# powermeter.net
KiCad netlist of a schematic drawn in EAGLE
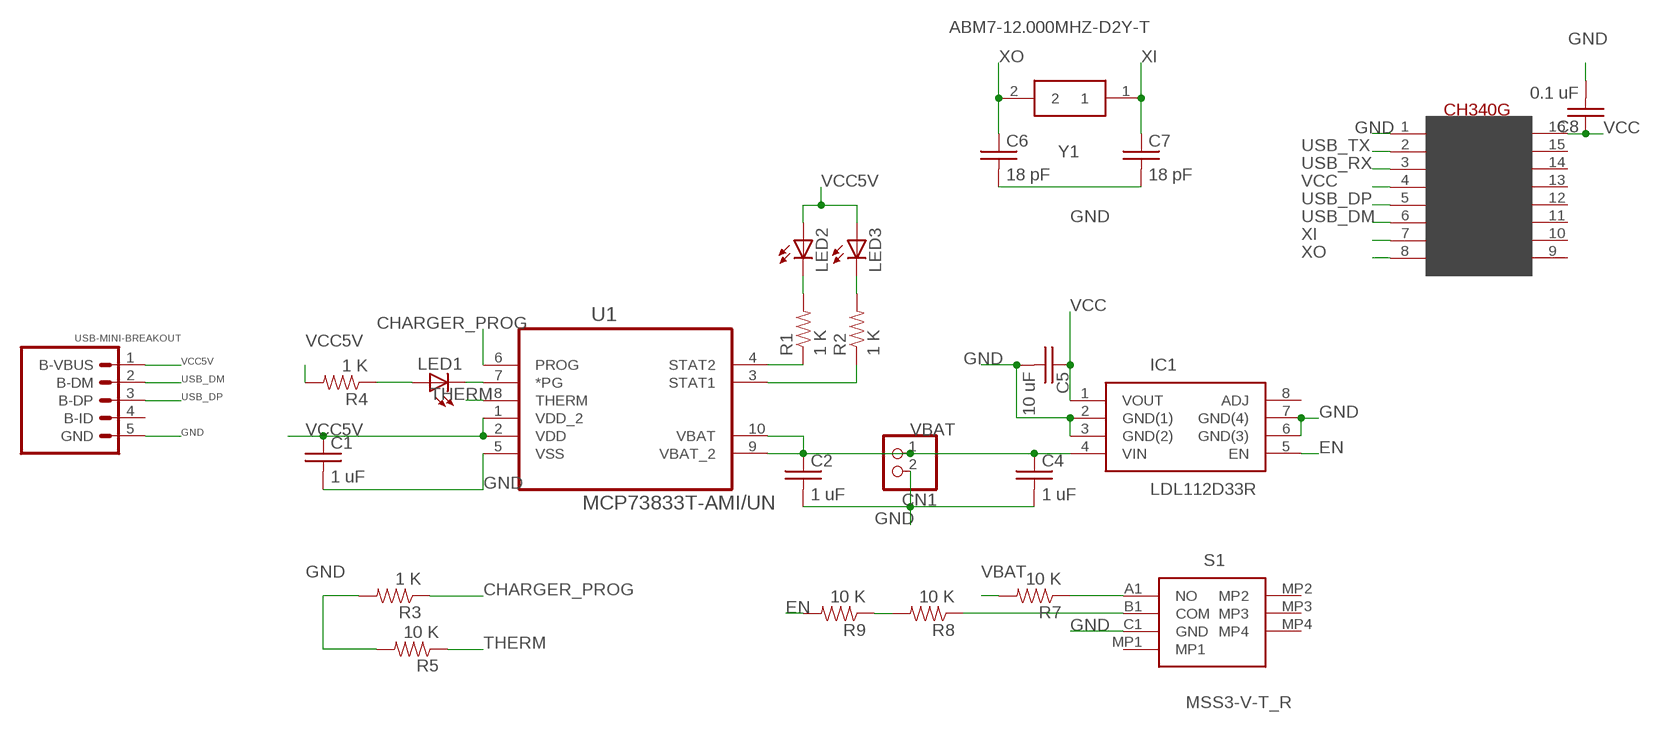
[diagram p0: schematic, sheet 1]
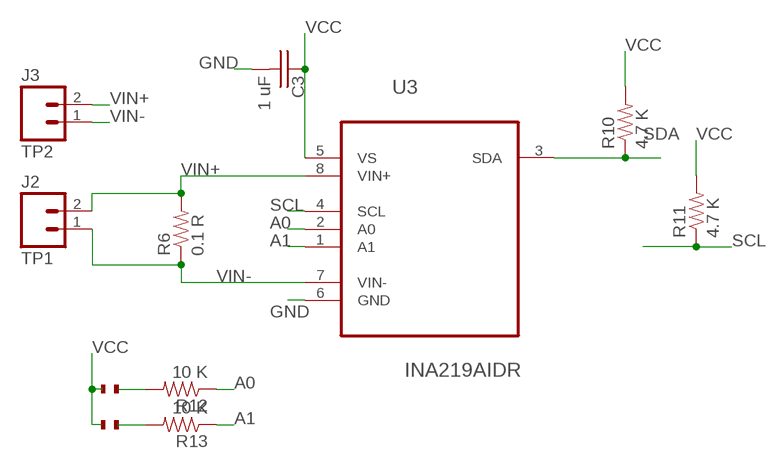
[diagram p1: schematic, sheet 2]
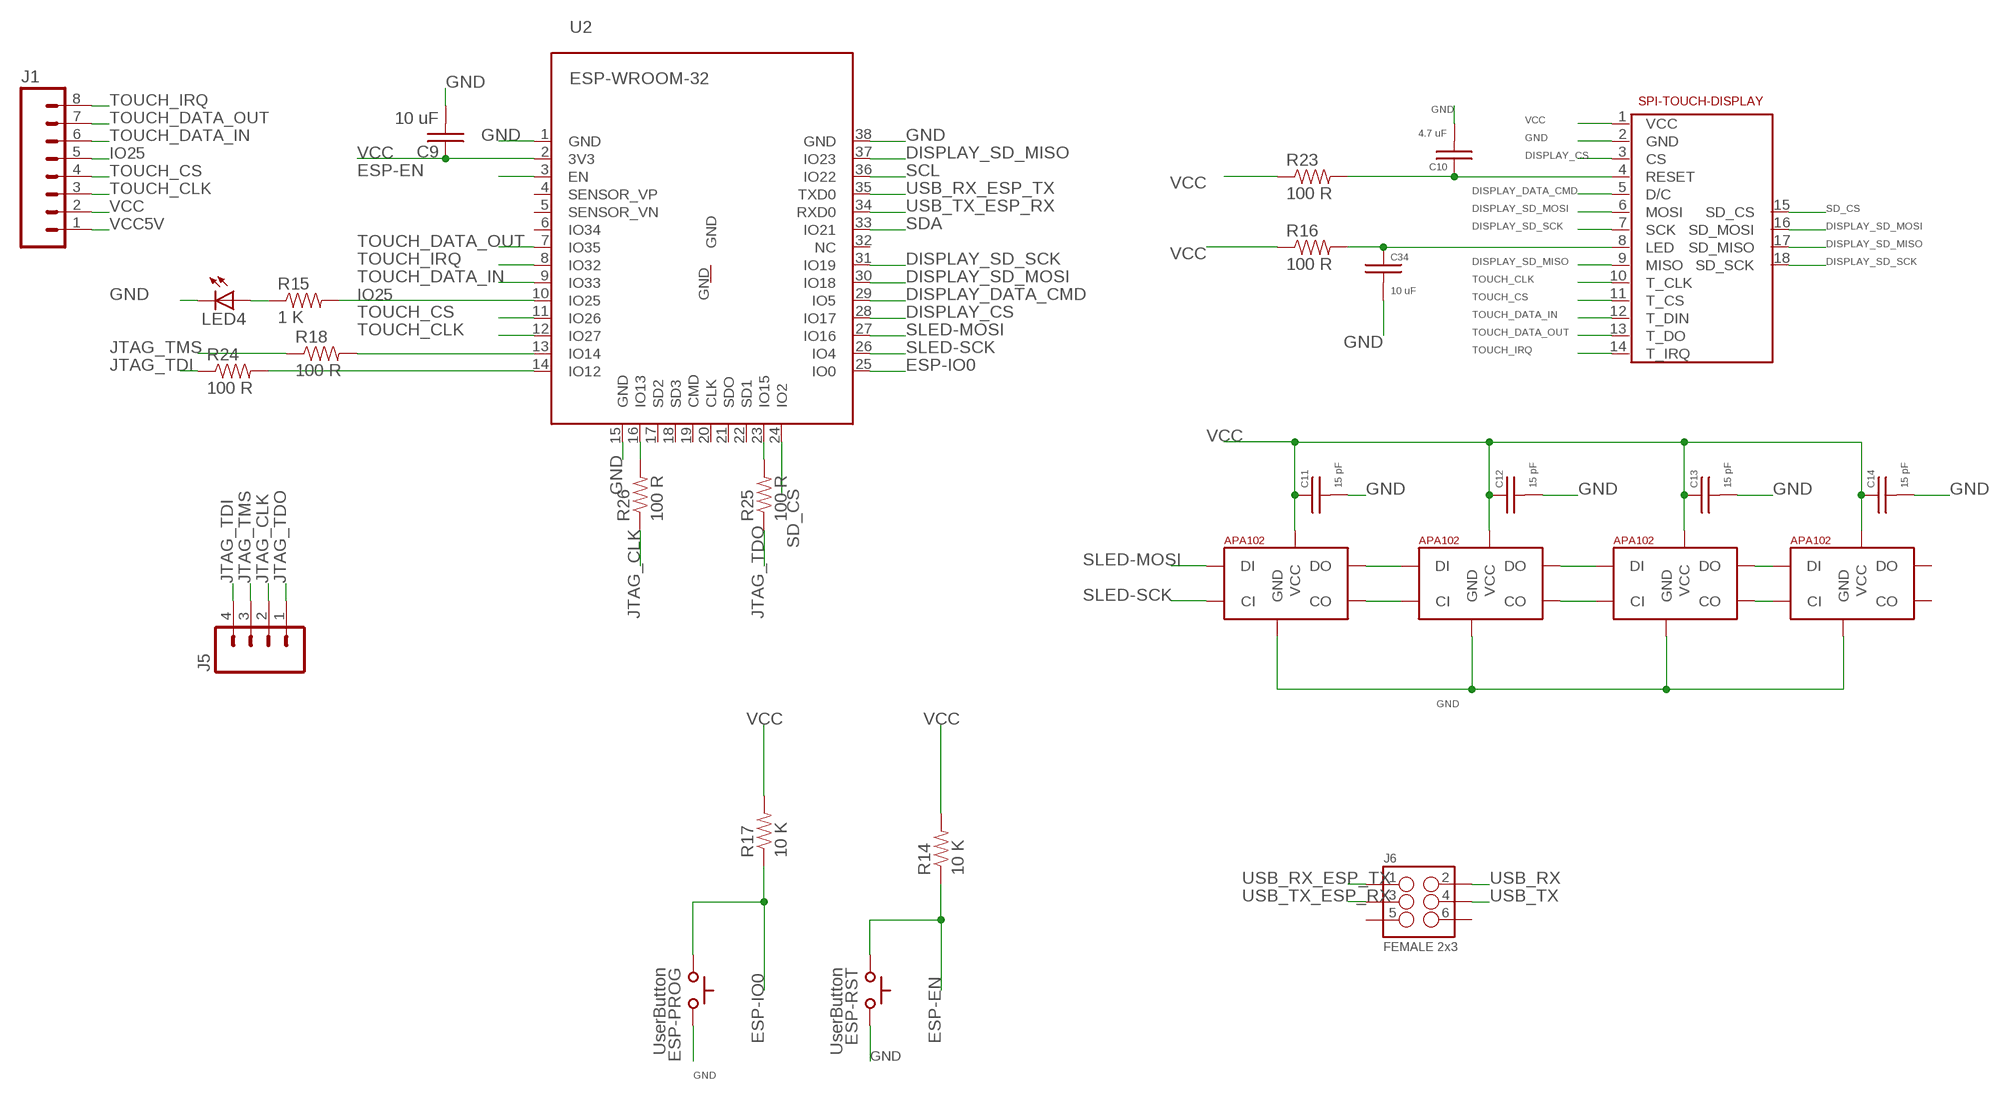
[diagram p2: schematic, sheet 3]

(export (version "E")
  (design (tool "Eeschema 10.0.6"))
  (components
    (comp (ref "C9")
      (value "10 uF")
      (footprint "eagle-import:C0805K")
      (libsource (lib "eagle-import") (part "C-USC0805K"))
    )
    (comp (ref "C10")
      (value "4.7 uF")
      (footprint "eagle-import:C0805")
      (libsource (lib "eagle-import") (part "C-USC0805"))
    )
    (comp (ref "C11")
      (value "15 pF")
      (footprint "eagle-import:C0805")
      (libsource (lib "eagle-import") (part "C-USC0805"))
    )
    (comp (ref "C12")
      (value "15 pF")
      (footprint "eagle-import:C0805")
      (libsource (lib "eagle-import") (part "C-USC0805"))
    )
    (comp (ref "C13")
      (value "15 pF")
      (footprint "eagle-import:C0805")
      (libsource (lib "eagle-import") (part "C-USC0805"))
    )
    (comp (ref "C14")
      (value "15 pF")
      (footprint "eagle-import:C0805")
      (libsource (lib "eagle-import") (part "C-USC0805"))
    )
    (comp (ref "C34")
      (value "10 uF")
      (footprint "eagle-import:C0805")
      (libsource (lib "eagle-import") (part "C-USC0805"))
    )
    (comp (ref "ESP-PROG")
      (value "UserButton")
      (footprint "eagle-import:TACTILE-2PIN-NARROW")
      (libsource (lib "eagle-import") (part "SWITCH_TACTILETACTILE-2PIN-NARROW"))
    )
    (comp (ref "ESP-RST")
      (value "UserButton")
      (footprint "eagle-import:TACTILE-2PIN-NARROW")
      (libsource (lib "eagle-import") (part "SWITCH_TACTILETACTILE-2PIN-NARROW"))
    )
    (comp (ref "J1")
      (value "M08LONGPADS")
      (footprint "eagle-import:1X08_LONGPADS")
      (libsource (lib "eagle-import") (part "M08LONGPADS"))
    )
    (comp (ref "J5")
      (value "M04LONGPADS")
      (footprint "eagle-import:1X04_LONGPADS")
      (libsource (lib "eagle-import") (part "M04LONGPADS"))
    )
    (comp (ref "J6")
      (value "FEMALE 2x3")
      (footprint "eagle-import:2X3")
      (libsource (lib "eagle-import") (part "M03X2FEMALE"))
    )
    (comp (ref "LED4")
      (value "LED1206")
      (footprint "eagle-import:LED-1206")
      (libsource (lib "eagle-import") (part "LED1206"))
    )
    (comp (ref "R14")
      (value "10 K")
      (footprint "eagle-import:R0805")
      (libsource (lib "eagle-import") (part "RESISTORR0805-RES"))
    )
    (comp (ref "R15")
      (value "1 K")
      (footprint "eagle-import:R0805")
      (libsource (lib "eagle-import") (part "RESISTORR0805-RES"))
    )
    (comp (ref "R16")
      (value "100 R")
      (footprint "eagle-import:R0805")
      (libsource (lib "eagle-import") (part "RESISTORR0805-RES"))
    )
    (comp (ref "R17")
      (value "10 K")
      (footprint "eagle-import:R0805")
      (libsource (lib "eagle-import") (part "RESISTORR0805-RES"))
    )
    (comp (ref "R18")
      (value "100 R")
      (footprint "eagle-import:R0805")
      (libsource (lib "eagle-import") (part "RESISTORR0805-RES"))
    )
    (comp (ref "R23")
      (value "100 R")
      (footprint "eagle-import:R0805")
      (libsource (lib "eagle-import") (part "RESISTORR0805-RES"))
    )
    (comp (ref "R24")
      (value "100 R")
      (footprint "eagle-import:R0805")
      (libsource (lib "eagle-import") (part "RESISTORR0805-RES"))
    )
    (comp (ref "R25")
      (value "100 R")
      (footprint "eagle-import:R0805")
      (libsource (lib "eagle-import") (part "RESISTORR0805-RES"))
    )
    (comp (ref "R26")
      (value "100 R")
      (footprint "eagle-import:R0805")
      (libsource (lib "eagle-import") (part "RESISTORR0805-RES"))
    )
    (comp (ref "U$3")
      (value "2.4-SPI-TFT-TOUCH-SSD-MODULE")
      (footprint "eagle-import:2.4-SPI-TFT-TOUCH-SSD-MODULE")
      (libsource (lib "eagle-import") (part "2.4-SPI-TFT-TOUCH-SSD-MODULE"))
    )
    (comp (ref "U$5")
      (value "APA1025050")
      (footprint "eagle-import:APA102_5050")
      (libsource (lib "eagle-import") (part "APA1025050"))
    )
    (comp (ref "U$6")
      (value "APA1025050")
      (footprint "eagle-import:APA102_5050")
      (libsource (lib "eagle-import") (part "APA1025050"))
    )
    (comp (ref "U$7")
      (value "APA1025050")
      (footprint "eagle-import:APA102_5050")
      (libsource (lib "eagle-import") (part "APA1025050"))
    )
    (comp (ref "U$8")
      (value "APA1025050")
      (footprint "eagle-import:APA102_5050")
      (libsource (lib "eagle-import") (part "APA1025050"))
    )
    (comp (ref "U2")
      (value "ESP-WROOM-32")
      (footprint "eagle-import:ESP-WROOM-32")
      (libsource (lib "eagle-import") (part "ESP-WROOM-32"))
    )
    (comp (ref "C1")
      (value "1 uF")
      (footprint "eagle-import:C0805K")
      (libsource (lib "eagle-import") (part "C-USC0805K"))
    )
    (comp (ref "C2")
      (value "1 uF")
      (footprint "eagle-import:C0805K")
      (libsource (lib "eagle-import") (part "C-USC0805K"))
    )
    (comp (ref "C4")
      (value "1 uF")
      (footprint "eagle-import:C0805K")
      (libsource (lib "eagle-import") (part "C-USC0805K"))
    )
    (comp (ref "C5")
      (value "10 uF")
      (footprint "eagle-import:C0805K")
      (libsource (lib "eagle-import") (part "C-USC0805K"))
    )
    (comp (ref "C6")
      (value "18 pF")
      (footprint "eagle-import:C0805K")
      (libsource (lib "eagle-import") (part "C-USC0805K"))
    )
    (comp (ref "C7")
      (value "18 pF")
      (footprint "eagle-import:C0805K")
      (libsource (lib "eagle-import") (part "C-USC0805K"))
    )
    (comp (ref "C8")
      (value "0.1 uF")
      (footprint "eagle-import:C0805K")
      (libsource (lib "eagle-import") (part "C-USC0805K"))
    )
    (comp (ref "CN1")
      (value "JST_2PIN-THM-RA")
      (footprint "eagle-import:JST-PH-2-THM-RA")
      (libsource (lib "eagle-import") (part "JST_2PIN-THM-RA"))
    )
    (comp (ref "IC1")
      (value "LDL112D33R")
      (footprint "eagle-import:SOIC127P600X175-8N")
      (libsource (lib "eagle-import") (part "LDL112D33R"))
    )
    (comp (ref "LED1")
      (value "LEDXZCFBB53W-8VF-2MA-LED")
      (footprint "eagle-import:LEDC1606X95N")
      (libsource (lib "eagle-import") (part "LEDXZCFBB53W-8VF-2MA-LED"))
    )
    (comp (ref "LED2")
      (value "LEDXZCFBB53W-8VF-2MA-LED")
      (footprint "eagle-import:LEDC1606X95N")
      (libsource (lib "eagle-import") (part "LEDXZCFBB53W-8VF-2MA-LED"))
    )
    (comp (ref "LED3")
      (value "LEDXZCFBB53W-8VF-2MA-LED")
      (footprint "eagle-import:LEDC1606X95N")
      (libsource (lib "eagle-import") (part "LEDXZCFBB53W-8VF-2MA-LED"))
    )
    (comp (ref "R1")
      (value "1 K")
      (footprint "eagle-import:R0805")
      (libsource (lib "eagle-import") (part "RESISTORR0805-RES"))
    )
    (comp (ref "R2")
      (value "1 K")
      (footprint "eagle-import:R0805")
      (libsource (lib "eagle-import") (part "RESISTORR0805-RES"))
    )
    (comp (ref "R3")
      (value "1 K")
      (footprint "eagle-import:R0805")
      (libsource (lib "eagle-import") (part "RESISTORR0805-RES"))
    )
    (comp (ref "R4")
      (value "1 K")
      (footprint "eagle-import:R0805")
      (libsource (lib "eagle-import") (part "RESISTORR0805-RES"))
    )
    (comp (ref "R5")
      (value "10 K")
      (footprint "eagle-import:R0805")
      (libsource (lib "eagle-import") (part "RESISTORR0805-RES"))
    )
    (comp (ref "R7")
      (value "10 K")
      (footprint "eagle-import:R0805")
      (libsource (lib "eagle-import") (part "RESISTORR0805-RES"))
    )
    (comp (ref "R8")
      (value "10 K")
      (footprint "eagle-import:R0805")
      (libsource (lib "eagle-import") (part "RESISTORR0805-RES"))
    )
    (comp (ref "R9")
      (value "10 K")
      (footprint "eagle-import:R0805")
      (libsource (lib "eagle-import") (part "RESISTORR0805-RES"))
    )
    (comp (ref "S1")
      (value "MSS3-V-T_R")
      (footprint "eagle-import:MSS3VTR")
      (fields
        (field (name "MANUFACTURER_PART_NUMBER") "MSS3-V-T/R")
        (field (name "MOUSER_PART_NUMBER") "113-MSS3-V-T/R")
      )
      (libsource (lib "eagle-import") (part "MSS3-V-T_R"))
    )
    (comp (ref "U$4")
      (value "CH340G")
      (footprint "eagle-import:SOIC16")
      (libsource (lib "eagle-import") (part "CH340G"))
    )
    (comp (ref "U1")
      (value "MCP73833T-AMI/UN")
      (footprint "eagle-import:SOP50P490X110-10N")
      (fields (field (name "MF") "Microchip"))
      (libsource (lib "eagle-import") (part "MCP73833T-AMI/UN"))
    )
    (comp (ref "USB-MINI-BREAKOUT")
      (value "USB-MINI-BREAKOUT")
      (footprint "eagle-import:1X05_LONGPADS")
      (libsource (lib "eagle-import") (part "USB-MINI-BREAKOUT"))
    )
    (comp (ref "Y1")
      (value "ABM7-12.000MHZ-D2Y-T")
      (footprint "eagle-import:ABM7")
      (fields
        (field (name "MOUSER_PART_NUMBER") "815-ABM7-12-D2Y-T")
        (field (name "RS_PART_NUMBER") "1710625P")
      )
      (libsource (lib "eagle-import") (part "ABM7-12.000MHZ-D2Y-T"))
    )
    (comp (ref "C3")
      (value "1 uF")
      (footprint "eagle-import:C0805K")
      (libsource (lib "eagle-import") (part "C-USC0805K"))
    )
    (comp (ref "J2")
      (value "TP1")
      (footprint "eagle-import:SCREWTERMINAL-3.5MM-2")
      (libsource (lib "eagle-import") (part "M023.5MM"))
    )
    (comp (ref "J3")
      (value "TP2")
      (footprint "eagle-import:1X02_LOCK_LONGPADS")
      (libsource (lib "eagle-import") (part "M02LOCK_LONGPADS"))
    )
    (comp (ref "R6")
      (value "0.1 R")
      (footprint "eagle-import:R2010")
      (libsource (lib "eagle-import") (part "RESISTOR2010"))
    )
    (comp (ref "R10")
      (value "4.7 K")
      (footprint "eagle-import:R0805")
      (libsource (lib "eagle-import") (part "RESISTORR0805-RES"))
    )
    (comp (ref "R11")
      (value "4.7 K")
      (footprint "eagle-import:R0805")
      (libsource (lib "eagle-import") (part "RESISTORR0805-RES"))
    )
    (comp (ref "R12")
      (value "10 K")
      (footprint "eagle-import:R0805")
      (libsource (lib "eagle-import") (part "RESISTORR0805-RES"))
    )
    (comp (ref "R13")
      (value "10 K")
      (footprint "eagle-import:R0805")
      (libsource (lib "eagle-import") (part "RESISTORR0805-RES"))
    )
    (comp (ref "U$1")
      (value "SURFACE_MOUNT_JUMP")
      (footprint "eagle-import:SURFACE_JUMPER")
      (libsource (lib "eagle-import") (part "SURFACE_MOUNT_JUMP"))
    )
    (comp (ref "U$2")
      (value "SURFACE_MOUNT_JUMP")
      (footprint "eagle-import:SURFACE_JUMPER")
      (libsource (lib "eagle-import") (part "SURFACE_MOUNT_JUMP"))
    )
    (comp (ref "U3")
      (value "INA219AIDR")
      (footprint "eagle-import:SOIC127P600X175-8N")
      (fields (field (name "MF") "Texas Instruments"))
      (libsource (lib "eagle-import") (part "INA219AIDR"))
    )
  )
  (nets
    (net (code "1") (name "A0") (class "Default")
      (node (ref "R12") (pin "1") (pinfunction "1_1") (pintype "passive"))
      (node (ref "U3") (pin "2") (pinfunction "A0_2") (pintype "input"))
    )
    (net (code "2") (name "A1") (class "Default")
      (node (ref "R13") (pin "1") (pinfunction "1_1") (pintype "passive"))
      (node (ref "U3") (pin "1") (pinfunction "A1_1") (pintype "input"))
    )
    (net (code "3") (name "CHARGER_PROG") (class "Default")
      (node (ref "R3") (pin "1") (pinfunction "1_1") (pintype "passive"))
      (node (ref "U1") (pin "6") (pinfunction "PROG_6") (pintype "input"))
    )
    (net (code "4") (name "DISPLAY_CS") (class "Default")
      (node (ref "U$3") (pin "3") (pinfunction "CS_3") (pintype "bidirectional"))
      (node (ref "U2") (pin "28") (pinfunction "IO17_28") (pintype "bidirectional"))
    )
    (net (code "5") (name "DISPLAY_DATA_CMD") (class "Default")
      (node (ref "U$3") (pin "5") (pinfunction "D/C_5") (pintype "bidirectional"))
      (node (ref "U2") (pin "29") (pinfunction "IO5_29") (pintype "bidirectional"))
    )
    (net (code "6") (name "DISPLAY_SD_MISO") (class "Default")
      (node (ref "U$3") (pin "17") (pinfunction "SD_MISO_17") (pintype "bidirectional"))
      (node (ref "U$3") (pin "9") (pinfunction "MISO_9") (pintype "bidirectional"))
      (node (ref "U2") (pin "37") (pinfunction "IO23_37") (pintype "bidirectional"))
    )
    (net (code "7") (name "DISPLAY_SD_MOSI") (class "Default")
      (node (ref "U$3") (pin "16") (pinfunction "SD_MOSI_16") (pintype "bidirectional"))
      (node (ref "U$3") (pin "6") (pinfunction "MOSI_6") (pintype "bidirectional"))
      (node (ref "U2") (pin "30") (pinfunction "IO18_30") (pintype "bidirectional"))
    )
    (net (code "8") (name "DISPLAY_SD_SCK") (class "Default")
      (node (ref "U$3") (pin "18") (pinfunction "SD_SCK_18") (pintype "bidirectional"))
      (node (ref "U$3") (pin "7") (pinfunction "SCK_7") (pintype "bidirectional"))
      (node (ref "U2") (pin "31") (pinfunction "IO19_31") (pintype "bidirectional"))
    )
    (net (code "9") (name "EN") (class "Default")
      (node (ref "IC1") (pin "5") (pinfunction "EN_5") (pintype "bidirectional"))
      (node (ref "R9") (pin "2") (pinfunction "2_2") (pintype "passive"))
    )
    (net (code "10") (name "ESP-EN") (class "Default")
      (node (ref "ESP-RST") (pin "P$2") (pinfunction "C_P$2") (pintype "passive"))
      (node (ref "R14") (pin "1") (pinfunction "1_1") (pintype "passive"))
      (node (ref "U2") (pin "3") (pinfunction "EN_3") (pintype "bidirectional"))
    )
    (net (code "11") (name "ESP-IO0") (class "Default")
      (node (ref "ESP-PROG") (pin "P$2") (pinfunction "C_P$2") (pintype "passive"))
      (node (ref "R17") (pin "1") (pinfunction "1_1") (pintype "passive"))
      (node (ref "U2") (pin "25") (pinfunction "IO0_25") (pintype "bidirectional"))
    )
    (net (code "12") (name "GND") (class "Default")
      (node (ref "C1") (pin "2") (pinfunction "2_2") (pintype "passive"))
      (node (ref "C10") (pin "2") (pinfunction "2_2") (pintype "passive"))
      (node (ref "C11") (pin "2") (pinfunction "2_2") (pintype "passive"))
      (node (ref "C12") (pin "2") (pinfunction "2_2") (pintype "passive"))
      (node (ref "C13") (pin "2") (pinfunction "2_2") (pintype "passive"))
      (node (ref "C14") (pin "2") (pinfunction "2_2") (pintype "passive"))
      (node (ref "C2") (pin "2") (pinfunction "2_2") (pintype "passive"))
      (node (ref "C3") (pin "2") (pinfunction "2_2") (pintype "passive"))
      (node (ref "C34") (pin "2") (pinfunction "2_2") (pintype "passive"))
      (node (ref "C4") (pin "2") (pinfunction "2_2") (pintype "passive"))
      (node (ref "C5") (pin "2") (pinfunction "2_2") (pintype "passive"))
      (node (ref "C6") (pin "2") (pinfunction "2_2") (pintype "passive"))
      (node (ref "C7") (pin "2") (pinfunction "2_2") (pintype "passive"))
      (node (ref "C8") (pin "2") (pinfunction "2_2") (pintype "passive"))
      (node (ref "C9") (pin "2") (pinfunction "2_2") (pintype "passive"))
      (node (ref "CN1") (pin "2") (pinfunction "1_2") (pintype "passive"))
      (node (ref "ESP-PROG") (pin "P$1") (pinfunction "A_P$1") (pintype "passive"))
      (node (ref "ESP-RST") (pin "P$1") (pinfunction "A_P$1") (pintype "passive"))
      (node (ref "IC1") (pin "2") (pinfunction "GND(1)_2") (pintype "bidirectional"))
      (node (ref "IC1") (pin "3") (pinfunction "GND(2)_3") (pintype "bidirectional"))
      (node (ref "IC1") (pin "6") (pinfunction "GND(3)_6") (pintype "bidirectional"))
      (node (ref "IC1") (pin "7") (pinfunction "GND(4)_7") (pintype "bidirectional"))
      (node (ref "LED4") (pin "C") (pinfunction "C_C") (pintype "output"))
      (node (ref "R3") (pin "2") (pinfunction "2_2") (pintype "passive"))
      (node (ref "R5") (pin "2") (pinfunction "2_2") (pintype "passive"))
      (node (ref "S1") (pin "C1") (pinfunction "GND_C1") (pintype "bidirectional"))
      (node (ref "U$3") (pin "2") (pinfunction "GND_2") (pintype "power_in"))
      (node (ref "U$4") (pin "1") (pinfunction "GND_1") (pintype "bidirectional"))
      (node (ref "U$5") (pin "6") (pinfunction "GND_6") (pintype "bidirectional"))
      (node (ref "U$6") (pin "6") (pinfunction "GND_6") (pintype "bidirectional"))
      (node (ref "U$7") (pin "6") (pinfunction "GND_6") (pintype "bidirectional"))
      (node (ref "U$8") (pin "6") (pinfunction "GND_6") (pintype "bidirectional"))
      (node (ref "U1") (pin "5") (pinfunction "VSS_5") (pintype "passive"))
      (node (ref "U2") (pin "1") (pinfunction "GND_1") (pintype "bidirectional"))
      (node (ref "U2") (pin "15") (pinfunction "GND_15") (pintype "bidirectional"))
      (node (ref "U2") (pin "38") (pinfunction "GND_38") (pintype "bidirectional"))
      (node (ref "U3") (pin "6") (pinfunction "GND_6") (pintype "passive"))
      (node (ref "USB-MINI-BREAKOUT") (pin "5") (pinfunction "GND_5") (pintype "power_in"))
    )
    (net (code "13") (name "IO25") (class "Default")
      (node (ref "J1") (pin "5") (pinfunction "5_5") (pintype "passive"))
      (node (ref "R15") (pin "2") (pinfunction "2_2") (pintype "passive"))
      (node (ref "U2") (pin "10") (pinfunction "IO25_10") (pintype "bidirectional"))
    )
    (net (code "14") (name "JTAG_CLK") (class "Default")
      (node (ref "J5") (pin "2") (pinfunction "2_2") (pintype "passive"))
      (node (ref "R26") (pin "1") (pinfunction "1_1") (pintype "passive"))
    )
    (net (code "15") (name "JTAG_TDI") (class "Default")
      (node (ref "J5") (pin "4") (pinfunction "4_4") (pintype "passive"))
      (node (ref "R24") (pin "1") (pinfunction "1_1") (pintype "passive"))
    )
    (net (code "16") (name "JTAG_TDO") (class "Default")
      (node (ref "J5") (pin "1") (pinfunction "1_1") (pintype "passive"))
      (node (ref "R25") (pin "1") (pinfunction "1_1") (pintype "passive"))
    )
    (net (code "17") (name "JTAG_TMS") (class "Default")
      (node (ref "J5") (pin "3") (pinfunction "3_3") (pintype "passive"))
      (node (ref "R18") (pin "1") (pinfunction "1_1") (pintype "passive"))
    )
    (net (code "18") (name "Net-(LED1-A)") (class "Default")
      (node (ref "LED1") (pin "1") (pinfunction "A_1") (pintype "input"))
      (node (ref "R4") (pin "1") (pinfunction "1_1") (pintype "passive"))
    )
    (net (code "19") (name "Net-(LED1-C)") (class "Default")
      (node (ref "LED1") (pin "2") (pinfunction "C_2") (pintype "output"))
      (node (ref "U1") (pin "7") (pinfunction "*PG_7") (pintype "input"))
    )
    (net (code "20") (name "Net-(LED2-C)") (class "Default")
      (node (ref "LED2") (pin "2") (pinfunction "C_2") (pintype "output"))
      (node (ref "R1") (pin "2") (pinfunction "2_2") (pintype "passive"))
    )
    (net (code "21") (name "Net-(LED3-C)") (class "Default")
      (node (ref "LED3") (pin "2") (pinfunction "C_2") (pintype "output"))
      (node (ref "R2") (pin "2") (pinfunction "2_2") (pintype "passive"))
    )
    (net (code "22") (name "Net-(LED4-PadA)") (class "Default")
      (node (ref "LED4") (pin "A") (pinfunction "A_A") (pintype "input"))
      (node (ref "R15") (pin "1") (pinfunction "1_1") (pintype "passive"))
    )
    (net (code "23") (name "Net-(R8-Pad2)") (class "Default")
      (node (ref "R8") (pin "2") (pinfunction "2_2") (pintype "passive"))
      (node (ref "R9") (pin "1") (pinfunction "1_1") (pintype "passive"))
    )
    (net (code "24") (name "Net-(R12-Pad2)") (class "Default")
      (node (ref "R12") (pin "2") (pinfunction "2_2") (pintype "passive"))
      (node (ref "U$1") (pin "2") (pinfunction "2_2") (pintype "bidirectional"))
    )
    (net (code "25") (name "Net-(R13-Pad2)") (class "Default")
      (node (ref "R13") (pin "2") (pinfunction "2_2") (pintype "passive"))
      (node (ref "U$2") (pin "2") (pinfunction "2_2") (pintype "bidirectional"))
    )
    (net (code "26") (name "Net-(S1-COM)") (class "Default")
      (node (ref "R8") (pin "1") (pinfunction "1_1") (pintype "passive"))
      (node (ref "S1") (pin "B1") (pinfunction "COM_B1") (pintype "bidirectional"))
    )
    (net (code "27") (name "Net-(S1-NO)") (class "Default")
      (node (ref "R7") (pin "1") (pinfunction "1_1") (pintype "passive"))
      (node (ref "S1") (pin "A1") (pinfunction "NO_A1") (pintype "bidirectional"))
    )
    (net (code "28") (name "Net-(U$3-LED)") (class "Default")
      (node (ref "C34") (pin "1") (pinfunction "1_1") (pintype "passive"))
      (node (ref "R16") (pin "2") (pinfunction "2_2") (pintype "passive"))
      (node (ref "U$3") (pin "8") (pinfunction "LED_8") (pintype "bidirectional"))
    )
    (net (code "29") (name "Net-(U$3-RESET)") (class "Default")
      (node (ref "C10") (pin "1") (pinfunction "1_1") (pintype "passive"))
      (node (ref "R23") (pin "2") (pinfunction "2_2") (pintype "passive"))
      (node (ref "U$3") (pin "4") (pinfunction "RESET_4") (pintype "bidirectional"))
    )
    (net (code "30") (name "Net-(U$5-CO)") (class "Default")
      (node (ref "U$5") (pin "2") (pinfunction "CO_2") (pintype "bidirectional"))
      (node (ref "U$6") (pin "5") (pinfunction "CI_5") (pintype "bidirectional"))
    )
    (net (code "31") (name "Net-(U$5-DO)") (class "Default")
      (node (ref "U$5") (pin "3") (pinfunction "DO_3") (pintype "bidirectional"))
      (node (ref "U$6") (pin "4") (pinfunction "DI_4") (pintype "bidirectional"))
    )
    (net (code "32") (name "Net-(U$6-CO)") (class "Default")
      (node (ref "U$6") (pin "2") (pinfunction "CO_2") (pintype "bidirectional"))
      (node (ref "U$7") (pin "5") (pinfunction "CI_5") (pintype "bidirectional"))
    )
    (net (code "33") (name "Net-(U$6-DO)") (class "Default")
      (node (ref "U$6") (pin "3") (pinfunction "DO_3") (pintype "bidirectional"))
      (node (ref "U$7") (pin "4") (pinfunction "DI_4") (pintype "bidirectional"))
    )
    (net (code "34") (name "Net-(U$7-CO)") (class "Default")
      (node (ref "U$7") (pin "2") (pinfunction "CO_2") (pintype "bidirectional"))
      (node (ref "U$8") (pin "5") (pinfunction "CI_5") (pintype "bidirectional"))
    )
    (net (code "35") (name "Net-(U$7-DO)") (class "Default")
      (node (ref "U$7") (pin "3") (pinfunction "DO_3") (pintype "bidirectional"))
      (node (ref "U$8") (pin "4") (pinfunction "DI_4") (pintype "bidirectional"))
    )
    (net (code "36") (name "Net-(U1-STAT1)") (class "Default")
      (node (ref "R2") (pin "1") (pinfunction "1_1") (pintype "passive"))
      (node (ref "U1") (pin "3") (pinfunction "STAT1_3") (pintype "output"))
    )
    (net (code "37") (name "Net-(U1-STAT2)") (class "Default")
      (node (ref "R1") (pin "1") (pinfunction "1_1") (pintype "passive"))
      (node (ref "U1") (pin "4") (pinfunction "STAT2_4") (pintype "output"))
    )
    (net (code "38") (name "Net-(U2-IO12)") (class "Default")
      (node (ref "R24") (pin "2") (pinfunction "2_2") (pintype "passive"))
      (node (ref "U2") (pin "14") (pinfunction "IO12_14") (pintype "bidirectional"))
    )
    (net (code "39") (name "Net-(U2-IO13)") (class "Default")
      (node (ref "R26") (pin "2") (pinfunction "2_2") (pintype "passive"))
      (node (ref "U2") (pin "16") (pinfunction "IO13_16") (pintype "bidirectional"))
    )
    (net (code "40") (name "Net-(U2-IO14)") (class "Default")
      (node (ref "R18") (pin "2") (pinfunction "2_2") (pintype "passive"))
      (node (ref "U2") (pin "13") (pinfunction "IO14_13") (pintype "bidirectional"))
    )
    (net (code "41") (name "Net-(U2-IO15)") (class "Default")
      (node (ref "R25") (pin "2") (pinfunction "2_2") (pintype "passive"))
      (node (ref "U2") (pin "23") (pinfunction "IO15_23") (pintype "bidirectional"))
    )
    (net (code "42") (name "SCL") (class "Default")
      (node (ref "R11") (pin "1") (pinfunction "1_1") (pintype "passive"))
      (node (ref "U2") (pin "36") (pinfunction "IO22_36") (pintype "bidirectional"))
      (node (ref "U3") (pin "4") (pinfunction "SCL_4") (pintype "input"))
    )
    (net (code "43") (name "SDA") (class "Default")
      (node (ref "R10") (pin "1") (pinfunction "1_1") (pintype "passive"))
      (node (ref "U2") (pin "33") (pinfunction "IO21_33") (pintype "bidirectional"))
      (node (ref "U3") (pin "3") (pinfunction "SDA_3") (pintype "bidirectional"))
    )
    (net (code "44") (name "SD_CS") (class "Default")
      (node (ref "U$3") (pin "15") (pinfunction "SD_CS_15") (pintype "bidirectional"))
      (node (ref "U2") (pin "24") (pinfunction "IO2_24") (pintype "bidirectional"))
    )
    (net (code "45") (name "SLED-MOSI") (class "Default")
      (node (ref "U$5") (pin "4") (pinfunction "DI_4") (pintype "bidirectional"))
      (node (ref "U2") (pin "27") (pinfunction "IO16_27") (pintype "bidirectional"))
    )
    (net (code "46") (name "SLED-SCK") (class "Default")
      (node (ref "U$5") (pin "5") (pinfunction "CI_5") (pintype "bidirectional"))
      (node (ref "U2") (pin "26") (pinfunction "IO4_26") (pintype "bidirectional"))
    )
    (net (code "47") (name "THERM") (class "Default")
      (node (ref "R5") (pin "1") (pinfunction "1_1") (pintype "passive"))
      (node (ref "U1") (pin "8") (pinfunction "THERM_8") (pintype "input"))
    )
    (net (code "48") (name "TOUCH_CLK") (class "Default")
      (node (ref "J1") (pin "3") (pinfunction "3_3") (pintype "passive"))
      (node (ref "U$3") (pin "10") (pinfunction "T_CLK_10") (pintype "bidirectional"))
      (node (ref "U2") (pin "12") (pinfunction "IO27_12") (pintype "bidirectional"))
    )
    (net (code "49") (name "TOUCH_CS") (class "Default")
      (node (ref "J1") (pin "4") (pinfunction "4_4") (pintype "passive"))
      (node (ref "U$3") (pin "11") (pinfunction "T_CS_11") (pintype "bidirectional"))
      (node (ref "U2") (pin "11") (pinfunction "IO26_11") (pintype "bidirectional"))
    )
    (net (code "50") (name "TOUCH_DATA_IN") (class "Default")
      (node (ref "J1") (pin "6") (pinfunction "6_6") (pintype "passive"))
      (node (ref "U$3") (pin "12") (pinfunction "T_DIN_12") (pintype "bidirectional"))
      (node (ref "U2") (pin "9") (pinfunction "IO33_9") (pintype "bidirectional"))
    )
    (net (code "51") (name "TOUCH_DATA_OUT") (class "Default")
      (node (ref "J1") (pin "7") (pinfunction "7_7") (pintype "passive"))
      (node (ref "U$3") (pin "13") (pinfunction "T_DO_13") (pintype "bidirectional"))
      (node (ref "U2") (pin "7") (pinfunction "IO35_7") (pintype "bidirectional"))
    )
    (net (code "52") (name "TOUCH_IRQ") (class "Default")
      (node (ref "J1") (pin "8") (pinfunction "8_8") (pintype "passive"))
      (node (ref "U$3") (pin "14") (pinfunction "T_IRQ_14") (pintype "bidirectional"))
      (node (ref "U2") (pin "8") (pinfunction "IO32_8") (pintype "bidirectional"))
    )
    (net (code "53") (name "USB_DM") (class "Default")
      (node (ref "U$4") (pin "6") (pinfunction "D-_6") (pintype "bidirectional"))
      (node (ref "USB-MINI-BREAKOUT") (pin "2") (pinfunction "B-DM_2") (pintype "bidirectional"))
    )
    (net (code "54") (name "USB_DP") (class "Default")
      (node (ref "U$4") (pin "5") (pinfunction "D+_5") (pintype "bidirectional"))
      (node (ref "USB-MINI-BREAKOUT") (pin "3") (pinfunction "B-DP_3") (pintype "bidirectional"))
    )
    (net (code "55") (name "USB_RX") (class "Default")
      (node (ref "J6") (pin "2") (pinfunction "2_2") (pintype "bidirectional"))
      (node (ref "U$4") (pin "3") (pinfunction "RX_3") (pintype "bidirectional"))
    )
    (net (code "56") (name "USB_RX_ESP_TX") (class "Default")
      (node (ref "J6") (pin "1") (pinfunction "1_1") (pintype "bidirectional"))
      (node (ref "U2") (pin "35") (pinfunction "TXD0_35") (pintype "bidirectional"))
    )
    (net (code "57") (name "USB_TX") (class "Default")
      (node (ref "J6") (pin "4") (pinfunction "4_4") (pintype "bidirectional"))
      (node (ref "U$4") (pin "2") (pinfunction "TX_2") (pintype "bidirectional"))
    )
    (net (code "58") (name "USB_TX_ESP_RX") (class "Default")
      (node (ref "J6") (pin "3") (pinfunction "3_3") (pintype "bidirectional"))
      (node (ref "U2") (pin "34") (pinfunction "RXD0_34") (pintype "bidirectional"))
    )
    (net (code "59") (name "VBAT") (class "Default")
      (node (ref "C2") (pin "1") (pinfunction "1_1") (pintype "passive"))
      (node (ref "C4") (pin "1") (pinfunction "1_1") (pintype "passive"))
      (node (ref "CN1") (pin "1") (pinfunction "2_1") (pintype "passive"))
      (node (ref "IC1") (pin "4") (pinfunction "VIN_4") (pintype "bidirectional"))
      (node (ref "R7") (pin "2") (pinfunction "2_2") (pintype "passive"))
      (node (ref "U1") (pin "10") (pinfunction "VBAT_10") (pintype "output"))
      (node (ref "U1") (pin "9") (pinfunction "VBAT_2_9") (pintype "output"))
    )
    (net (code "60") (name "VCC") (class "Default")
      (node (ref "C11") (pin "1") (pinfunction "1_1") (pintype "passive"))
      (node (ref "C12") (pin "1") (pinfunction "1_1") (pintype "passive"))
      (node (ref "C13") (pin "1") (pinfunction "1_1") (pintype "passive"))
      (node (ref "C14") (pin "1") (pinfunction "1_1") (pintype "passive"))
      (node (ref "C3") (pin "1") (pinfunction "1_1") (pintype "passive"))
      (node (ref "C5") (pin "1") (pinfunction "1_1") (pintype "passive"))
      (node (ref "C8") (pin "1") (pinfunction "1_1") (pintype "passive"))
      (node (ref "C9") (pin "1") (pinfunction "1_1") (pintype "passive"))
      (node (ref "IC1") (pin "1") (pinfunction "VOUT_1") (pintype "bidirectional"))
      (node (ref "J1") (pin "2") (pinfunction "2_2") (pintype "passive"))
      (node (ref "R10") (pin "2") (pinfunction "2_2") (pintype "passive"))
      (node (ref "R11") (pin "2") (pinfunction "2_2") (pintype "passive"))
      (node (ref "R14") (pin "2") (pinfunction "2_2") (pintype "passive"))
      (node (ref "R16") (pin "1") (pinfunction "1_1") (pintype "passive"))
      (node (ref "R17") (pin "2") (pinfunction "2_2") (pintype "passive"))
      (node (ref "R23") (pin "1") (pinfunction "1_1") (pintype "passive"))
      (node (ref "U$1") (pin "1") (pinfunction "1_1") (pintype "bidirectional"))
      (node (ref "U$2") (pin "1") (pinfunction "1_1") (pintype "bidirectional"))
      (node (ref "U$3") (pin "1") (pinfunction "VCC_1") (pintype "power_in"))
      (node (ref "U$4") (pin "16") (pinfunction "VCC_16") (pintype "bidirectional"))
      (node (ref "U$4") (pin "4") (pinfunction "V3_4") (pintype "bidirectional"))
      (node (ref "U$5") (pin "1") (pinfunction "VCC_1") (pintype "bidirectional"))
      (node (ref "U$6") (pin "1") (pinfunction "VCC_1") (pintype "bidirectional"))
      (node (ref "U$7") (pin "1") (pinfunction "VCC_1") (pintype "bidirectional"))
      (node (ref "U$8") (pin "1") (pinfunction "VCC_1") (pintype "bidirectional"))
      (node (ref "U2") (pin "2") (pinfunction "3V3_2") (pintype "bidirectional"))
      (node (ref "U3") (pin "5") (pinfunction "VS_5") (pintype "power_in"))
    )
    (net (code "61") (name "VCC5V") (class "Default")
      (node (ref "C1") (pin "1") (pinfunction "1_1") (pintype "passive"))
      (node (ref "J1") (pin "1") (pinfunction "1_1") (pintype "passive"))
      (node (ref "LED2") (pin "1") (pinfunction "A_1") (pintype "input"))
      (node (ref "LED3") (pin "1") (pinfunction "A_1") (pintype "input"))
      (node (ref "R4") (pin "2") (pinfunction "2_2") (pintype "passive"))
      (node (ref "U1") (pin "1") (pinfunction "VDD_2_1") (pintype "power_in"))
      (node (ref "U1") (pin "2") (pinfunction "VDD_2") (pintype "power_in"))
      (node (ref "USB-MINI-BREAKOUT") (pin "1") (pinfunction "B-VBUS_1") (pintype "power_in"))
    )
    (net (code "62") (name "VIN+") (class "Default")
      (node (ref "J2") (pin "2") (pinfunction "2_2") (pintype "passive"))
      (node (ref "J3") (pin "2") (pinfunction "2_2") (pintype "passive"))
      (node (ref "R6") (pin "2") (pinfunction "2_2") (pintype "passive"))
      (node (ref "U3") (pin "8") (pinfunction "VIN+_8") (pintype "power_in"))
    )
    (net (code "63") (name "VIN-") (class "Default")
      (node (ref "J2") (pin "1") (pinfunction "1_1") (pintype "passive"))
      (node (ref "J3") (pin "1") (pinfunction "1_1") (pintype "passive"))
      (node (ref "R6") (pin "1") (pinfunction "1_1") (pintype "passive"))
      (node (ref "U3") (pin "7") (pinfunction "VIN-_7") (pintype "power_in"))
    )
    (net (code "64") (name "XI") (class "Default")
      (node (ref "C7") (pin "1") (pinfunction "1_1") (pintype "passive"))
      (node (ref "U$4") (pin "7") (pinfunction "XI_7") (pintype "bidirectional"))
      (node (ref "Y1") (pin "1") (pinfunction "1_1") (pintype "bidirectional"))
    )
    (net (code "65") (name "XO") (class "Default")
      (node (ref "C6") (pin "1") (pinfunction "1_1") (pintype "passive"))
      (node (ref "U$4") (pin "8") (pinfunction "XO_8") (pintype "bidirectional"))
      (node (ref "Y1") (pin "2") (pinfunction "2_2") (pintype "bidirectional"))
    )
    (net (code "66") (name "unconnected-(IC1-ADJ-Pad8)") (class "Default")
      (node (ref "IC1") (pin "8") (pinfunction "ADJ_8") (pintype "bidirectional"))
    )
    (net (code "67") (name "unconnected-(J6-Pad5)") (class "Default")
      (node (ref "J6") (pin "5") (pinfunction "5_5") (pintype "bidirectional"))
    )
    (net (code "68") (name "unconnected-(J6-Pad6)") (class "Default")
      (node (ref "J6") (pin "6") (pinfunction "6_6") (pintype "bidirectional"))
    )
    (net (code "69") (name "unconnected-(S1-PadMP1)") (class "Default")
      (node (ref "S1") (pin "MP1") (pinfunction "MP1_MP1") (pintype "bidirectional"))
    )
    (net (code "70") (name "unconnected-(S1-PadMP2)") (class "Default")
      (node (ref "S1") (pin "MP2") (pinfunction "MP2_MP2") (pintype "bidirectional"))
    )
    (net (code "71") (name "unconnected-(S1-PadMP3)") (class "Default")
      (node (ref "S1") (pin "MP3") (pinfunction "MP3_MP3") (pintype "bidirectional"))
    )
    (net (code "72") (name "unconnected-(S1-PadMP4)") (class "Default")
      (node (ref "S1") (pin "MP4") (pinfunction "MP4_MP4") (pintype "bidirectional"))
    )
    (net (code "73") (name "unconnected-(U$4-CTS-Pad9)") (class "Default")
      (node (ref "U$4") (pin "9") (pinfunction "CTS_9") (pintype "bidirectional"))
    )
    (net (code "74") (name "unconnected-(U$4-DCD-Pad12)") (class "Default")
      (node (ref "U$4") (pin "12") (pinfunction "DCD_12") (pintype "bidirectional"))
    )
    (net (code "75") (name "unconnected-(U$4-DSR-Pad10)") (class "Default")
      (node (ref "U$4") (pin "10") (pinfunction "DSR_10") (pintype "bidirectional"))
    )
    (net (code "76") (name "unconnected-(U$4-DTR-Pad13)") (class "Default")
      (node (ref "U$4") (pin "13") (pinfunction "DTR_13") (pintype "bidirectional"))
    )
    (net (code "77") (name "unconnected-(U$4-RI-Pad11)") (class "Default")
      (node (ref "U$4") (pin "11") (pinfunction "RI_11") (pintype "bidirectional"))
    )
    (net (code "78") (name "unconnected-(U$4-RS232-Pad15)") (class "Default")
      (node (ref "U$4") (pin "15") (pinfunction "RS232_15") (pintype "bidirectional"))
    )
    (net (code "79") (name "unconnected-(U$4-RTS-Pad14)") (class "Default")
      (node (ref "U$4") (pin "14") (pinfunction "RTS_14") (pintype "bidirectional"))
    )
    (net (code "80") (name "unconnected-(U$8-CO-Pad2)") (class "Default")
      (node (ref "U$8") (pin "2") (pinfunction "CO_2") (pintype "bidirectional"))
    )
    (net (code "81") (name "unconnected-(U$8-DO-Pad3)") (class "Default")
      (node (ref "U$8") (pin "3") (pinfunction "DO_3") (pintype "bidirectional"))
    )
    (net (code "82") (name "unconnected-(U2-CLK-Pad20)") (class "Default")
      (node (ref "U2") (pin "20") (pinfunction "CLK_20") (pintype "bidirectional"))
    )
    (net (code "83") (name "unconnected-(U2-CMD-Pad19)") (class "Default")
      (node (ref "U2") (pin "19") (pinfunction "CMD_19") (pintype "bidirectional"))
    )
    (net (code "84") (name "unconnected-(U2-IO34-Pad6)") (class "Default")
      (node (ref "U2") (pin "6") (pinfunction "IO34_6") (pintype "bidirectional"))
    )
    (net (code "85") (name "unconnected-(U2-NC-Pad32)") (class "Default")
      (node (ref "U2") (pin "32") (pinfunction "NC_32") (pintype "bidirectional"))
    )
    (net (code "86") (name "unconnected-(U2-PadGND)") (class "Default")
      (node (ref "U2") (pin "GND") (pinfunction "GND_GND") (pintype "bidirectional"))
    )
    (net (code "87") (name "unconnected-(U2-SD1-Pad22)") (class "Default")
      (node (ref "U2") (pin "22") (pinfunction "SD1_22") (pintype "bidirectional"))
    )
    (net (code "88") (name "unconnected-(U2-SD2-Pad17)") (class "Default")
      (node (ref "U2") (pin "17") (pinfunction "SD2_17") (pintype "bidirectional"))
    )
    (net (code "89") (name "unconnected-(U2-SD3-Pad18)") (class "Default")
      (node (ref "U2") (pin "18") (pinfunction "SD3_18") (pintype "bidirectional"))
    )
    (net (code "90") (name "unconnected-(U2-SDO-Pad21)") (class "Default")
      (node (ref "U2") (pin "21") (pinfunction "SDO_21") (pintype "bidirectional"))
    )
    (net (code "91") (name "unconnected-(U2-SENSOR_VN-Pad5)") (class "Default")
      (node (ref "U2") (pin "5") (pinfunction "SENSOR_VN_5") (pintype "bidirectional"))
    )
    (net (code "92") (name "unconnected-(U2-SENSOR_VP-Pad4)") (class "Default")
      (node (ref "U2") (pin "4") (pinfunction "SENSOR_VP_4") (pintype "bidirectional"))
    )
    (net (code "93") (name "unconnected-(USB-MINI-BREAKOUT-B-ID-Pad4)") (class "Default")
      (node (ref "USB-MINI-BREAKOUT") (pin "4") (pinfunction "B-ID_4") (pintype "passive"))
    )
  )
)
